# TESTI2C.net
KiCad netlist of a schematic drawn in EAGLE
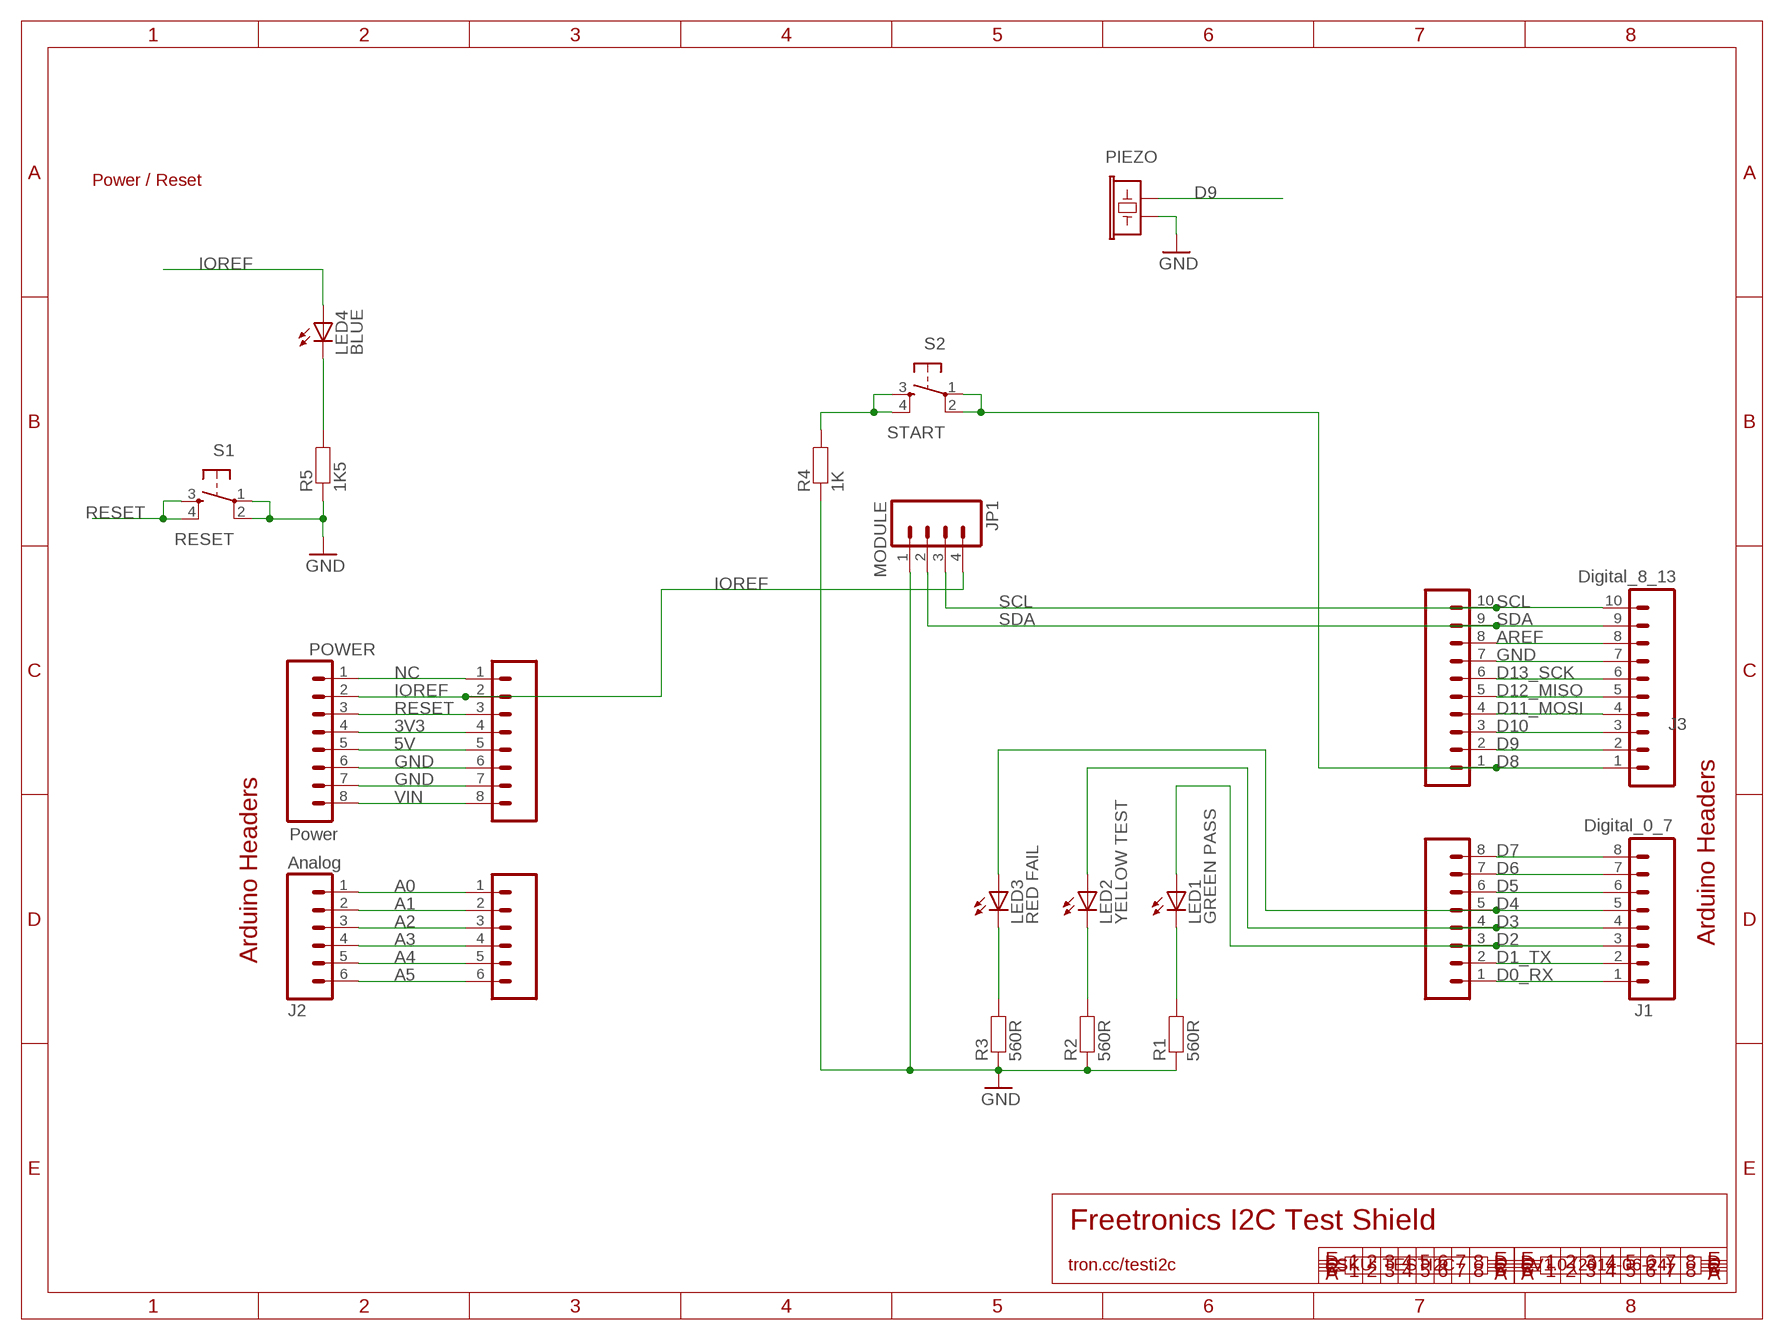
[diagram p0: schematic, sheet 1]

(export (version "E")
  (design (tool "Eeschema 10.0.6"))
  (components
    (comp (ref "J1")
      (value "Digital_0_7")
      (footprint "eagle-import:1X08")
      (libsource (lib "eagle-import") (part "M08"))
    )
    (comp (ref "J2")
      (value "Analog")
      (footprint "eagle-import:1X06")
      (libsource (lib "eagle-import") (part "M06SIP"))
    )
    (comp (ref "J3")
      (value "Digital_8_13")
      (footprint "eagle-import:1X10")
      (libsource (lib "eagle-import") (part "M100.1"))
    )
    (comp (ref "JP1")
      (value "MODULE")
      (footprint "eagle-import:1X04")
      (libsource (lib "eagle-import") (part "M04PTH"))
    )
    (comp (ref "LED1")
      (value "GREEN PASS")
      (footprint "eagle-import:LED-0603")
      (libsource (lib "eagle-import") (part "LED0603"))
    )
    (comp (ref "LED2")
      (value "YELLOW TEST")
      (footprint "eagle-import:LED-0603")
      (libsource (lib "eagle-import") (part "LED0603"))
    )
    (comp (ref "LED3")
      (value "RED FAIL")
      (footprint "eagle-import:LED-0603")
      (libsource (lib "eagle-import") (part "LED0603"))
    )
    (comp (ref "LED4")
      (value "BLUE")
      (footprint "eagle-import:LED-0603")
      (libsource (lib "eagle-import") (part "LED0603"))
    )
    (comp (ref "PIEZO")
      (value "BUZZERSMD12X12")
      (footprint "eagle-import:BUZZER-12X12-SMT")
      (libsource (lib "eagle-import") (part "BUZZERSMD12X12"))
    )
    (comp (ref "POWER")
      (value "Power")
      (footprint "eagle-import:1X08")
      (libsource (lib "eagle-import") (part "M08"))
    )
    (comp (ref "R1")
      (value "560R")
      (footprint "eagle-import:0603")
      (libsource (lib "eagle-import") (part "RESISTOR0603"))
    )
    (comp (ref "R2")
      (value "560R")
      (footprint "eagle-import:0603")
      (libsource (lib "eagle-import") (part "RESISTOR0603"))
    )
    (comp (ref "R3")
      (value "560R")
      (footprint "eagle-import:0603")
      (libsource (lib "eagle-import") (part "RESISTOR0603"))
    )
    (comp (ref "R4")
      (value "1K")
      (footprint "eagle-import:0603")
      (libsource (lib "eagle-import") (part "RESISTOR0603"))
    )
    (comp (ref "R5")
      (value "1K5")
      (footprint "eagle-import:0603")
      (libsource (lib "eagle-import") (part "RESISTOR0603"))
    )
    (comp (ref "S1")
      (value "RESET")
      (footprint "eagle-import:TACTILE-PTH")
      (libsource (lib "eagle-import") (part "TAC_SWITCHPTH"))
    )
    (comp (ref "S2")
      (value "START")
      (footprint "eagle-import:TACTILE-PTH")
      (libsource (lib "eagle-import") (part "TAC_SWITCHPTH"))
    )
    (comp (ref "SL1")
      (value "Digital_0_7")
      (footprint "eagle-import:1X08")
      (libsource (lib "eagle-import") (part "M08"))
    )
    (comp (ref "SL2")
      (value "Analog")
      (footprint "eagle-import:1X06")
      (libsource (lib "eagle-import") (part "M06SIP"))
    )
    (comp (ref "SL3")
      (value "Digital_8_13")
      (footprint "eagle-import:1X10")
      (libsource (lib "eagle-import") (part "M100.1"))
    )
    (comp (ref "SLP")
      (value "Power")
      (footprint "eagle-import:1X08")
      (libsource (lib "eagle-import") (part "M08"))
    )
  )
  (nets
    (net (code "1") (name "/3V3") (class "Default")
      (node (ref "POWER") (pin "4") (pinfunction "4_4") (pintype "passive"))
      (node (ref "SLP") (pin "4") (pinfunction "4_4") (pintype "passive"))
    )
    (net (code "2") (name "/5V") (class "Default")
      (node (ref "POWER") (pin "5") (pinfunction "5_5") (pintype "passive"))
      (node (ref "SLP") (pin "5") (pinfunction "5_5") (pintype "passive"))
    )
    (net (code "3") (name "/A0") (class "Default")
      (node (ref "J2") (pin "1") (pinfunction "1_1") (pintype "passive"))
      (node (ref "SL2") (pin "1") (pinfunction "1_1") (pintype "passive"))
    )
    (net (code "4") (name "/A1") (class "Default")
      (node (ref "J2") (pin "2") (pinfunction "2_2") (pintype "passive"))
      (node (ref "SL2") (pin "2") (pinfunction "2_2") (pintype "passive"))
    )
    (net (code "5") (name "/A2") (class "Default")
      (node (ref "J2") (pin "3") (pinfunction "3_3") (pintype "passive"))
      (node (ref "SL2") (pin "3") (pinfunction "3_3") (pintype "passive"))
    )
    (net (code "6") (name "/A3") (class "Default")
      (node (ref "J2") (pin "4") (pinfunction "4_4") (pintype "passive"))
      (node (ref "SL2") (pin "4") (pinfunction "4_4") (pintype "passive"))
    )
    (net (code "7") (name "/A4") (class "Default")
      (node (ref "J2") (pin "5") (pinfunction "5_5") (pintype "passive"))
      (node (ref "SL2") (pin "5") (pinfunction "5_5") (pintype "passive"))
    )
    (net (code "8") (name "/A5") (class "Default")
      (node (ref "J2") (pin "6") (pinfunction "6_6") (pintype "passive"))
      (node (ref "SL2") (pin "6") (pinfunction "6_6") (pintype "passive"))
    )
    (net (code "9") (name "/AREF") (class "Default")
      (node (ref "J3") (pin "8") (pinfunction "8_8") (pintype "passive"))
      (node (ref "SL3") (pin "8") (pinfunction "8_8") (pintype "passive"))
    )
    (net (code "10") (name "/D0_RX") (class "Default")
      (node (ref "J1") (pin "1") (pinfunction "1_1") (pintype "passive"))
      (node (ref "SL1") (pin "1") (pinfunction "1_1") (pintype "passive"))
    )
    (net (code "11") (name "/D1_TX") (class "Default")
      (node (ref "J1") (pin "2") (pinfunction "2_2") (pintype "passive"))
      (node (ref "SL1") (pin "2") (pinfunction "2_2") (pintype "passive"))
    )
    (net (code "12") (name "/D2") (class "Default")
      (node (ref "J1") (pin "3") (pinfunction "3_3") (pintype "passive"))
      (node (ref "LED1") (pin "A") (pinfunction "A_A") (pintype "passive"))
      (node (ref "SL1") (pin "3") (pinfunction "3_3") (pintype "passive"))
    )
    (net (code "13") (name "/D3") (class "Default")
      (node (ref "J1") (pin "4") (pinfunction "4_4") (pintype "passive"))
      (node (ref "LED2") (pin "A") (pinfunction "A_A") (pintype "passive"))
      (node (ref "SL1") (pin "4") (pinfunction "4_4") (pintype "passive"))
    )
    (net (code "14") (name "/D4") (class "Default")
      (node (ref "J1") (pin "5") (pinfunction "5_5") (pintype "passive"))
      (node (ref "LED3") (pin "A") (pinfunction "A_A") (pintype "passive"))
      (node (ref "SL1") (pin "5") (pinfunction "5_5") (pintype "passive"))
    )
    (net (code "15") (name "/D5") (class "Default")
      (node (ref "J1") (pin "6") (pinfunction "6_6") (pintype "passive"))
      (node (ref "SL1") (pin "6") (pinfunction "6_6") (pintype "passive"))
    )
    (net (code "16") (name "/D6") (class "Default")
      (node (ref "J1") (pin "7") (pinfunction "7_7") (pintype "passive"))
      (node (ref "SL1") (pin "7") (pinfunction "7_7") (pintype "passive"))
    )
    (net (code "17") (name "/D7") (class "Default")
      (node (ref "J1") (pin "8") (pinfunction "8_8") (pintype "passive"))
      (node (ref "SL1") (pin "8") (pinfunction "8_8") (pintype "passive"))
    )
    (net (code "18") (name "/D8") (class "Default")
      (node (ref "J3") (pin "1") (pinfunction "1_1") (pintype "passive"))
      (node (ref "S2") (pin "1") (pinfunction "1_1") (pintype "passive"))
      (node (ref "S2") (pin "2") (pinfunction "2_2") (pintype "passive"))
      (node (ref "SL3") (pin "1") (pinfunction "1_1") (pintype "passive"))
    )
    (net (code "19") (name "/D9") (class "Default")
      (node (ref "J3") (pin "2") (pinfunction "2_2") (pintype "passive"))
      (node (ref "PIEZO") (pin "2") (pinfunction "2_2") (pintype "passive"))
      (node (ref "SL3") (pin "2") (pinfunction "2_2") (pintype "passive"))
    )
    (net (code "20") (name "/D10") (class "Default")
      (node (ref "J3") (pin "3") (pinfunction "3_3") (pintype "passive"))
      (node (ref "SL3") (pin "3") (pinfunction "3_3") (pintype "passive"))
    )
    (net (code "21") (name "/D11_MOSI") (class "Default")
      (node (ref "J3") (pin "4") (pinfunction "4_4") (pintype "passive"))
      (node (ref "SL3") (pin "4") (pinfunction "4_4") (pintype "passive"))
    )
    (net (code "22") (name "/D12_MISO") (class "Default")
      (node (ref "J3") (pin "5") (pinfunction "5_5") (pintype "passive"))
      (node (ref "SL3") (pin "5") (pinfunction "5_5") (pintype "passive"))
    )
    (net (code "23") (name "/D13_SCK") (class "Default")
      (node (ref "J3") (pin "6") (pinfunction "6_6") (pintype "passive"))
      (node (ref "SL3") (pin "6") (pinfunction "6_6") (pintype "passive"))
    )
    (net (code "24") (name "/IOREF") (class "Default")
      (node (ref "JP1") (pin "4") (pinfunction "4_4") (pintype "passive"))
      (node (ref "LED4") (pin "A") (pinfunction "A_A") (pintype "passive"))
      (node (ref "POWER") (pin "2") (pinfunction "2_2") (pintype "passive"))
      (node (ref "SLP") (pin "2") (pinfunction "2_2") (pintype "passive"))
    )
    (net (code "25") (name "/NC") (class "Default")
      (node (ref "POWER") (pin "1") (pinfunction "1_1") (pintype "passive"))
      (node (ref "SLP") (pin "1") (pinfunction "1_1") (pintype "passive"))
    )
    (net (code "26") (name "/RESET") (class "Default")
      (node (ref "POWER") (pin "3") (pinfunction "3_3") (pintype "passive"))
      (node (ref "S1") (pin "3") (pinfunction "3_3") (pintype "passive"))
      (node (ref "S1") (pin "4") (pinfunction "4_4") (pintype "passive"))
      (node (ref "SLP") (pin "3") (pinfunction "3_3") (pintype "passive"))
    )
    (net (code "27") (name "/SCL") (class "Default")
      (node (ref "J3") (pin "10") (pinfunction "10_10") (pintype "passive"))
      (node (ref "JP1") (pin "3") (pinfunction "3_3") (pintype "passive"))
      (node (ref "SL3") (pin "10") (pinfunction "10_10") (pintype "passive"))
    )
    (net (code "28") (name "/SDA") (class "Default")
      (node (ref "J3") (pin "9") (pinfunction "9_9") (pintype "passive"))
      (node (ref "JP1") (pin "2") (pinfunction "2_2") (pintype "passive"))
      (node (ref "SL3") (pin "9") (pinfunction "9_9") (pintype "passive"))
    )
    (net (code "29") (name "/VIN") (class "Default")
      (node (ref "POWER") (pin "8") (pinfunction "8_8") (pintype "passive"))
      (node (ref "SLP") (pin "8") (pinfunction "8_8") (pintype "passive"))
    )
    (net (code "30") (name "GND") (class "Default")
      (node (ref "J3") (pin "7") (pinfunction "7_7") (pintype "passive"))
      (node (ref "JP1") (pin "1") (pinfunction "1_1") (pintype "passive"))
      (node (ref "PIEZO") (pin "1") (pinfunction "1_1") (pintype "passive"))
      (node (ref "POWER") (pin "6") (pinfunction "6_6") (pintype "passive"))
      (node (ref "POWER") (pin "7") (pinfunction "7_7") (pintype "passive"))
      (node (ref "R1") (pin "1") (pinfunction "1_1") (pintype "passive"))
      (node (ref "R2") (pin "1") (pinfunction "1_1") (pintype "passive"))
      (node (ref "R3") (pin "1") (pinfunction "1_1") (pintype "passive"))
      (node (ref "R4") (pin "1") (pinfunction "1_1") (pintype "passive"))
      (node (ref "R5") (pin "1") (pinfunction "1_1") (pintype "passive"))
      (node (ref "S1") (pin "1") (pinfunction "1_1") (pintype "passive"))
      (node (ref "S1") (pin "2") (pinfunction "2_2") (pintype "passive"))
      (node (ref "SL3") (pin "7") (pinfunction "7_7") (pintype "passive"))
      (node (ref "SLP") (pin "6") (pinfunction "6_6") (pintype "passive"))
      (node (ref "SLP") (pin "7") (pinfunction "7_7") (pintype "passive"))
    )
    (net (code "31") (name "Net-(LED1-PadC)") (class "Default")
      (node (ref "LED1") (pin "C") (pinfunction "C_C") (pintype "passive"))
      (node (ref "R1") (pin "2") (pinfunction "2_2") (pintype "passive"))
    )
    (net (code "32") (name "Net-(LED2-PadC)") (class "Default")
      (node (ref "LED2") (pin "C") (pinfunction "C_C") (pintype "passive"))
      (node (ref "R2") (pin "2") (pinfunction "2_2") (pintype "passive"))
    )
    (net (code "33") (name "Net-(LED3-PadC)") (class "Default")
      (node (ref "LED3") (pin "C") (pinfunction "C_C") (pintype "passive"))
      (node (ref "R3") (pin "2") (pinfunction "2_2") (pintype "passive"))
    )
    (net (code "34") (name "Net-(LED4-PadC)") (class "Default")
      (node (ref "LED4") (pin "C") (pinfunction "C_C") (pintype "passive"))
      (node (ref "R5") (pin "2") (pinfunction "2_2") (pintype "passive"))
    )
    (net (code "35") (name "Net-(R4-Pad2)") (class "Default")
      (node (ref "R4") (pin "2") (pinfunction "2_2") (pintype "passive"))
      (node (ref "S2") (pin "3") (pinfunction "3_3") (pintype "passive"))
      (node (ref "S2") (pin "4") (pinfunction "4_4") (pintype "passive"))
    )
  )
)
